# motordriver-v5_0_LC-filter.net
KiCad netlist of a schematic drawn in Altium Designer
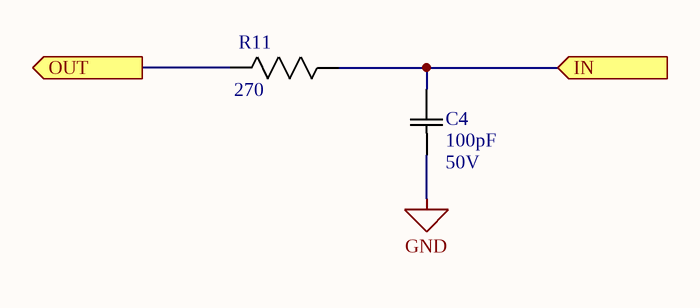
[diagram p0: motordriver-v5.0_LC-filter.SchDoc]

(export (version "E")
  (design (tool "Eeschema 10.0.6"))
  (components
    (comp (ref "C4")
      (value "100pF")
      (footprint "0603")
      (description "CAP CER 100PF 50V X7R 0603/0805")
      (fields (field (name "TOLERANCE") "10%") (field (name "RATING") "50V"))
      (libsource (lib "AltiumLibraries") (part "CAP 100pF 50V"))
    )
    (comp (ref "R11")
      (value "270")
      (footprint "0603")
      (description "RES SMD 270 OHM 1% 1/8W 0603/0805")
      (fields (field (name "TOLERANCE") "1%"))
      (libsource (lib "AltiumLibraries") (part "RES 270.0 1/8W - 1%"))
    )
  )
  (nets
    (net (code "1") (name "/IN") (class "Default")
      (node (ref "C4") (pin "2") (pinfunction "C2_2") (pintype "passive"))
      (node (ref "R11") (pin "1") (pinfunction "R1_1") (pintype "passive"))
    )
    (net (code "2") (name "/OUT") (class "Default")
      (node (ref "R11") (pin "2") (pinfunction "R2_2") (pintype "passive"))
    )
    (net (code "3") (name "GND") (class "Default")
      (node (ref "C4") (pin "1") (pinfunction "C1_1") (pintype "passive"))
    )
  )
)
